# Laser_main.net
KiCad netlist of a schematic drawn in Altium Designer
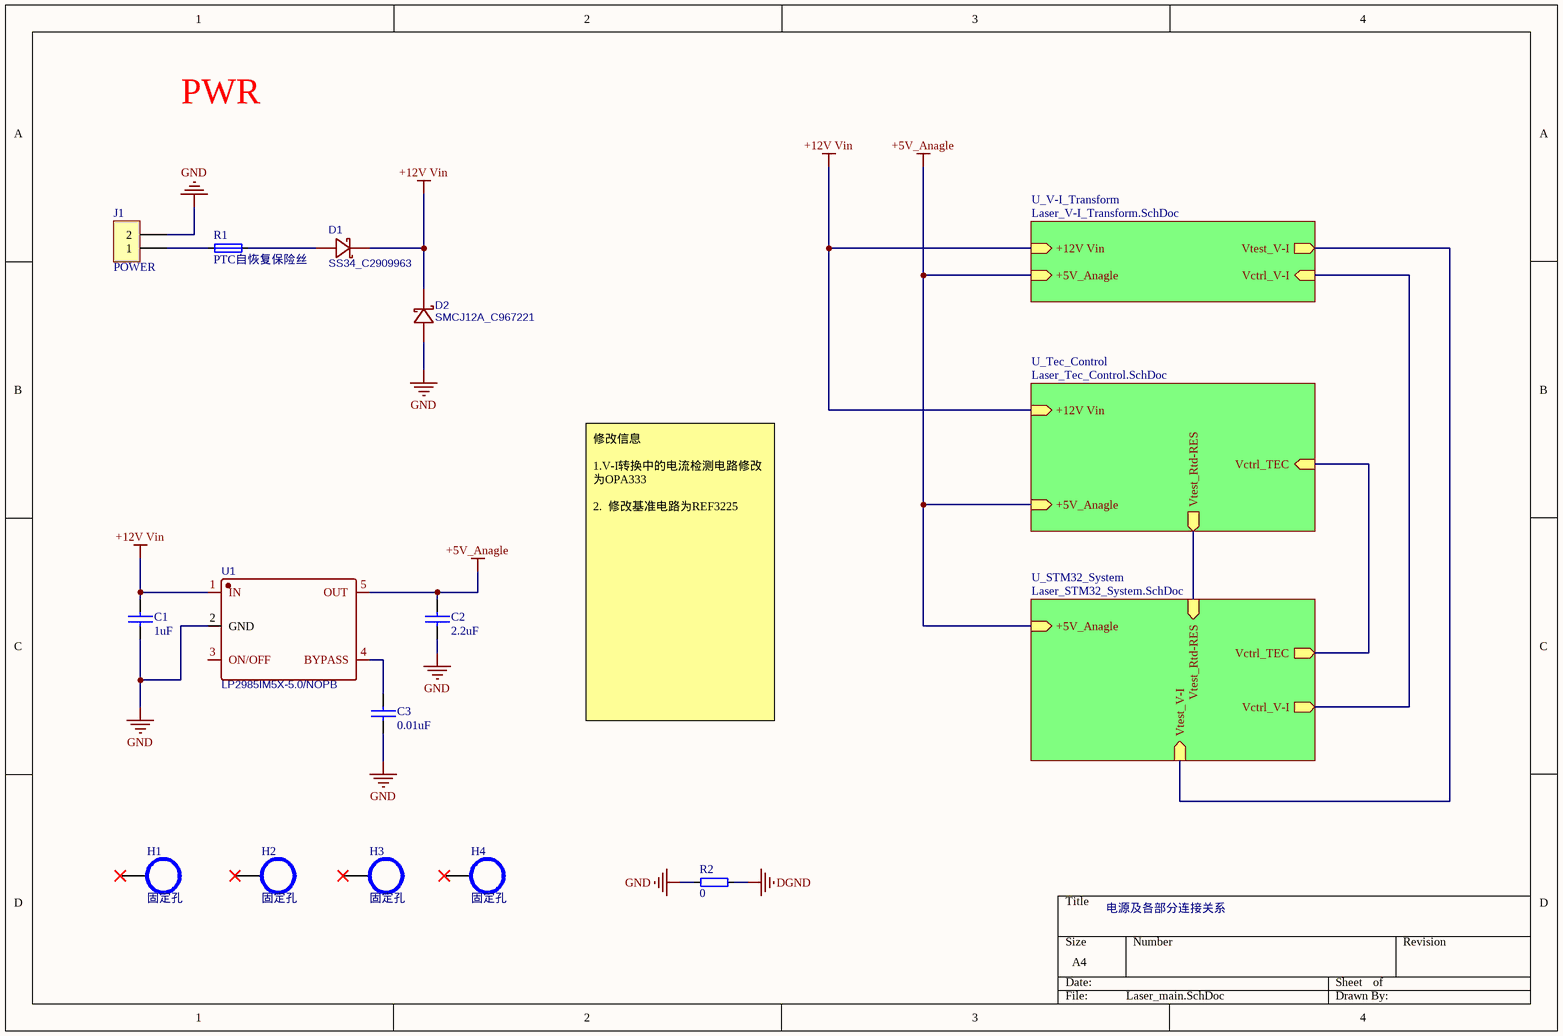
[diagram p0: Laser_main.SchDoc]

(export (version "E")
  (design (tool "Eeschema 10.0.6"))
  (components
    (comp (ref "C1")
      (value "1uF")
      (footprint "C 0603_M")
      (description "Capacitor")
      (libsource (lib "Laser Controller") (part "普通电容"))
    )
    (comp (ref "C2")
      (value "2.2uF")
      (footprint "C 0603_M")
      (description "Capacitor")
      (libsource (lib "Laser Controller") (part "普通电容"))
    )
    (comp (ref "C3")
      (value "0.01uF")
      (footprint "C 0603_M")
      (description "Capacitor")
      (libsource (lib "Laser Controller") (part "普通电容"))
    )
    (comp (ref "D1")
      (value "SS34_C2909963")
      (footprint "SMA_L4.2-W2.7-LS5.0-RD")
      (fields
        (field (name "BOM_SUPPLIER PART") "C2909963")
        (field (name "BOM_MANUFACTURER PART") "SS34")
        (field (name "CONTRIBUTOR") "LCSC")
      )
      (libsource (lib "Laser Controller") (part "SS34_C2909963"))
    )
    (comp (ref "D2")
      (value "SMCJ12A_C967221")
      (footprint "SMC_L6.9-W5.9-LS8.0-RD")
      (fields
        (field (name "BOM_SUPPLIER PART") "C967221")
        (field (name "BOM_MANUFACTURER PART") "SMCJ12A")
        (field (name "CONTRIBUTOR") "LCSC")
      )
      (libsource (lib "Laser Controller") (part "SMCJ12A_C967221"))
    )
    (comp (ref "H1") (value "固定孔") (footprint "铜柱孔3") (libsource (lib "Laser Controller") (part "固定孔")))
    (comp (ref "H2") (value "固定孔") (footprint "铜柱孔3") (libsource (lib "Laser Controller") (part "固定孔")))
    (comp (ref "H3") (value "固定孔") (footprint "铜柱孔3") (libsource (lib "Laser Controller") (part "固定孔")))
    (comp (ref "H4") (value "固定孔") (footprint "铜柱孔3") (libsource (lib "Laser Controller") (part "固定孔")))
    (comp (ref "J1")
      (value "POWER")
      (footprint "KF128-5.08-2P")
      (description "jointbar")
      (libsource (lib "Laser Controller") (part "SIP2"))
    )
    (comp (ref "R1")
      (value "PTC自恢复保险丝")
      (footprint "0805R")
      (libsource (lib "Laser Controller") (part "PTC自恢复保险丝"))
    )
    (comp (ref "R2")
      (value "0")
      (footprint "0603R")
      (description "电阻精度为0.1%")
      (libsource (lib "Laser Controller") (part "普通电阻"))
    )
    (comp (ref "U1")
      (value "LP2985IM5X-5.0/NOPB")
      (footprint "SOT-23-5_L3.0-W1.7-P0.95-LS2.8-BR")
      (fields (field (name "BOM_SUPPLIER PART") "C73908") (field (name "CONTRIBUTOR") "LCSC"))
      (libsource (lib "Laser Controller") (part "LP2985IM5X-5.0/NOPB"))
    )
  )
  (nets
    (net (code "1") (name "+5V_Anagle") (class "Default")
      (node (ref "C2") (pin "1") (pinfunction "1_1") (pintype "passive"))
      (node (ref "U1") (pin "5") (pinfunction "OUT_5") (pintype "passive"))
    )
    (net (code "2") (name "+12V Vin") (class "Default")
      (node (ref "C1") (pin "1") (pinfunction "1_1") (pintype "passive"))
      (node (ref "D1") (pin "1") (pinfunction "1_1") (pintype "passive"))
      (node (ref "D2") (pin "1") (pinfunction "C_1") (pintype "passive"))
      (node (ref "U1") (pin "1") (pinfunction "IN_1") (pintype "passive"))
    )
    (net (code "7") (name "DGND") (class "Default")
      (node (ref "R2") (pin "1") (pinfunction "1_1") (pintype "passive"))
    )
    (net (code "8") (name "GND") (class "Default")
      (node (ref "C1") (pin "2") (pinfunction "2_2") (pintype "passive"))
      (node (ref "C2") (pin "2") (pinfunction "2_2") (pintype "passive"))
      (node (ref "C3") (pin "2") (pinfunction "2_2") (pintype "passive"))
      (node (ref "D2") (pin "2") (pinfunction "A_2") (pintype "passive"))
      (node (ref "J1") (pin "2") (pinfunction "2_2") (pintype "passive"))
      (node (ref "R2") (pin "2") (pinfunction "2_2") (pintype "passive"))
      (node (ref "U1") (pin "2") (pinfunction "GND_2") (pintype "passive"))
    )
    (net (code "9") (name "Net-(D1-Pad2)") (class "Default")
      (node (ref "D1") (pin "2") (pinfunction "2_2") (pintype "passive"))
      (node (ref "R1") (pin "2") (pinfunction "2_2") (pintype "passive"))
    )
    (net (code "10") (name "Net-(J1-Pad1)") (class "Default")
      (node (ref "J1") (pin "1") (pinfunction "1_1") (pintype "passive"))
      (node (ref "R1") (pin "1") (pinfunction "1_1") (pintype "passive"))
    )
    (net (code "11") (name "Net-(U1-BYPASS)") (class "Default")
      (node (ref "C3") (pin "1") (pinfunction "1_1") (pintype "passive"))
      (node (ref "U1") (pin "4") (pinfunction "BYPASS_4") (pintype "passive"))
    )
    (net (code "12") (name "unconnected-(H1-Pad11)") (class "Default")
      (node (ref "H1") (pin "11") (pinfunction "11_11") (pintype "passive+no_connect"))
    )
    (net (code "13") (name "unconnected-(H2-Pad11)") (class "Default")
      (node (ref "H2") (pin "11") (pinfunction "11_11") (pintype "passive+no_connect"))
    )
    (net (code "14") (name "unconnected-(H3-Pad11)") (class "Default")
      (node (ref "H3") (pin "11") (pinfunction "11_11") (pintype "passive+no_connect"))
    )
    (net (code "15") (name "unconnected-(H4-Pad11)") (class "Default")
      (node (ref "H4") (pin "11") (pinfunction "11_11") (pintype "passive+no_connect"))
    )
    (net (code "16") (name "unconnected-(U1-ON{slash}OFF-Pad3)") (class "Default")
      (node (ref "U1") (pin "3") (pinfunction "ON/OFF_3") (pintype "passive"))
    )
  )
)
